# pomodoro-timer-shield.net
KiCad netlist of a schematic drawn in EAGLE
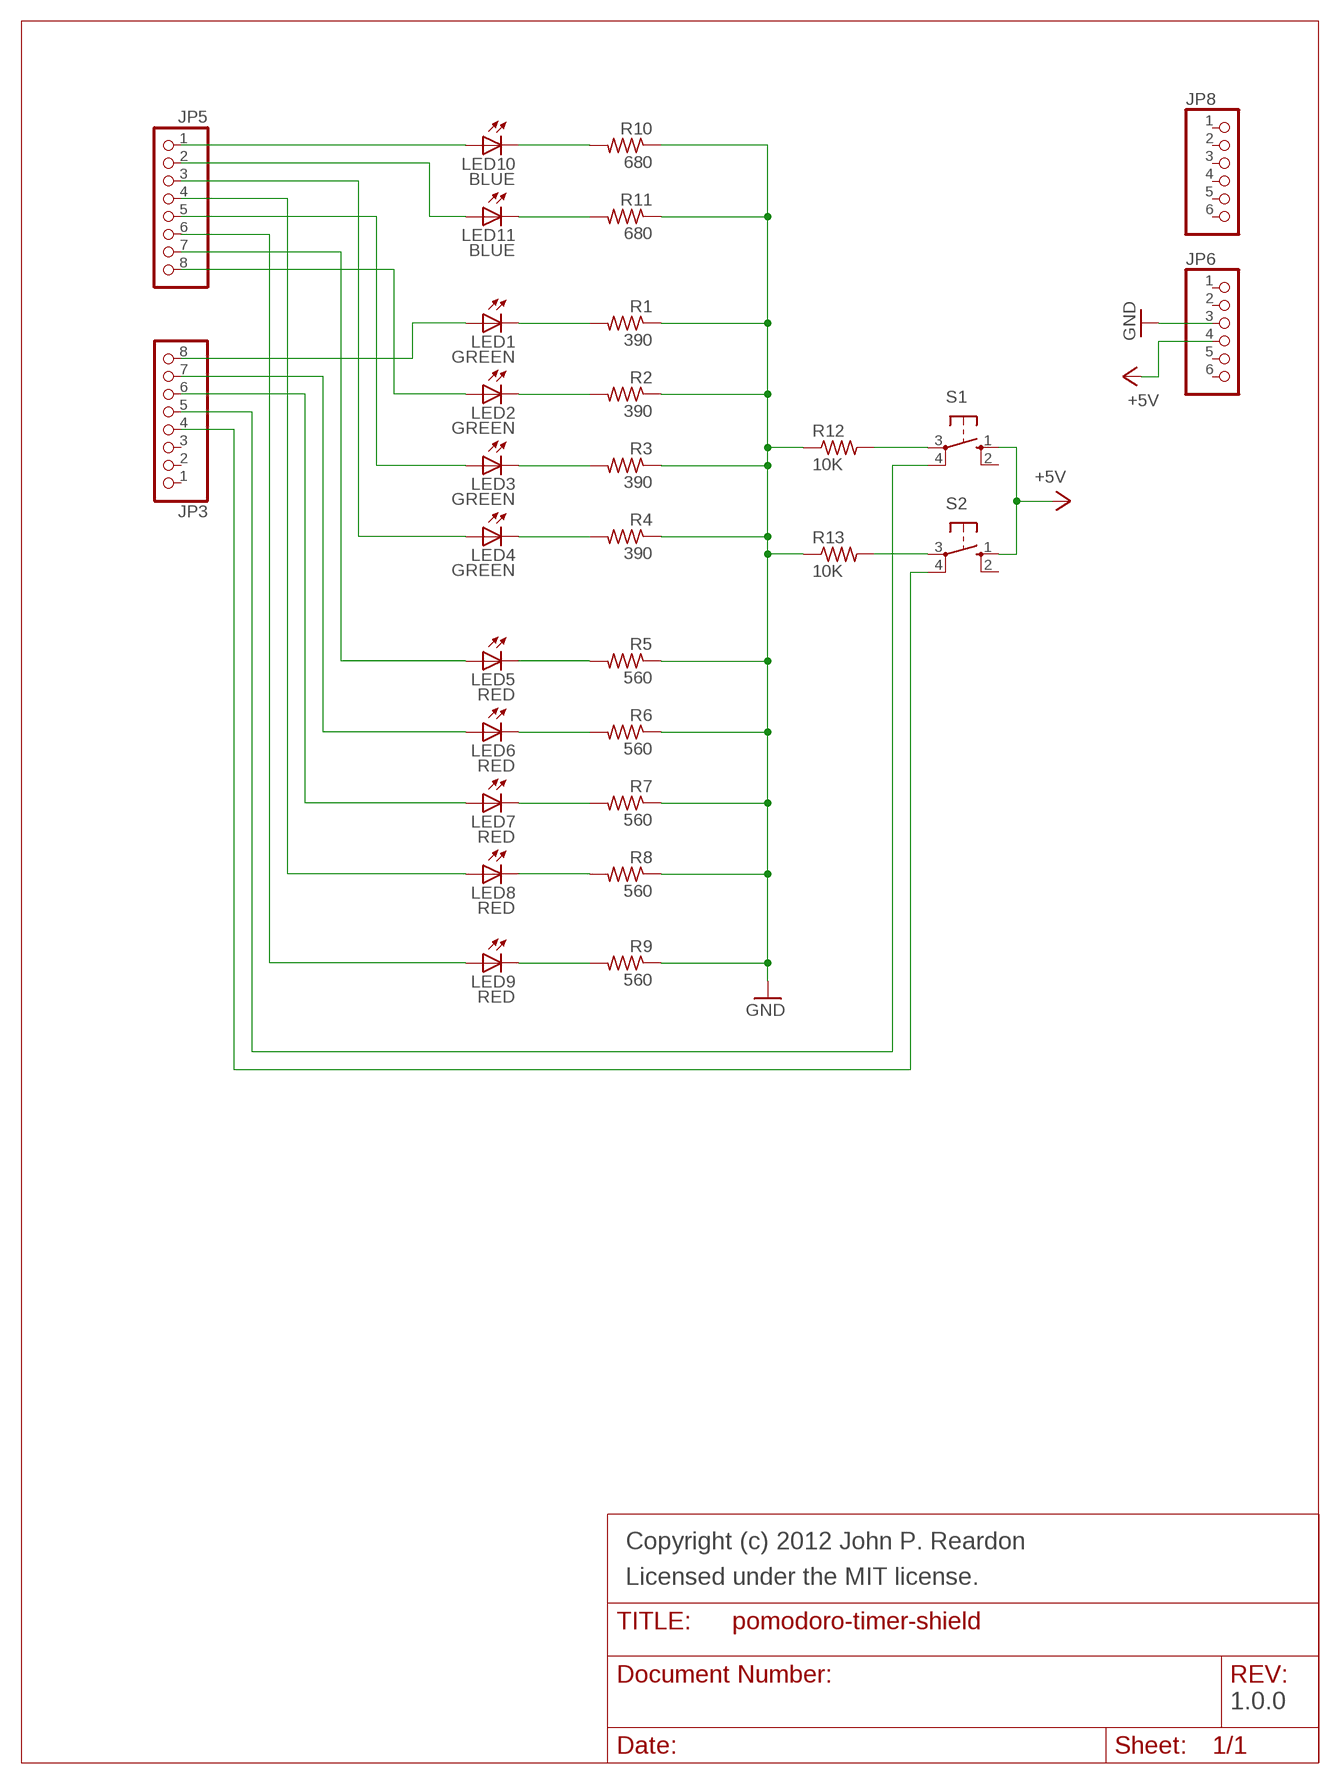
[diagram p0: schematic, sheet 1]

(export (version "E")
  (design (tool "Eeschema 10.0.6"))
  (components
    (comp (ref "JP3")
      (value "PINHD-1X8CLEANBIG")
      (footprint "eagle-import:1X08-CLEANBIG")
      (libsource (lib "eagle-import") (part "PINHD-1X8CLEANBIG"))
    )
    (comp (ref "JP5")
      (value "PINHD-1X8CLEANBIG")
      (footprint "eagle-import:1X08-CLEANBIG")
      (libsource (lib "eagle-import") (part "PINHD-1X8CLEANBIG"))
    )
    (comp (ref "JP6")
      (value "PINHD-1X6CB")
      (footprint "eagle-import:1X06-CLEANBIG")
      (libsource (lib "eagle-import") (part "PINHD-1X6CB"))
    )
    (comp (ref "JP8")
      (value "PINHD-1X6CB")
      (footprint "eagle-import:1X06-CLEANBIG")
      (libsource (lib "eagle-import") (part "PINHD-1X6CB"))
    )
    (comp (ref "LED1")
      (value "GREEN")
      (footprint "eagle-import:LED3MM")
      (libsource (lib "eagle-import") (part "LED3MM"))
    )
    (comp (ref "LED2")
      (value "GREEN")
      (footprint "eagle-import:LED3MM")
      (libsource (lib "eagle-import") (part "LED3MM"))
    )
    (comp (ref "LED3")
      (value "GREEN")
      (footprint "eagle-import:LED3MM")
      (libsource (lib "eagle-import") (part "LED3MM"))
    )
    (comp (ref "LED4")
      (value "GREEN")
      (footprint "eagle-import:LED3MM")
      (libsource (lib "eagle-import") (part "LED3MM"))
    )
    (comp (ref "LED5")
      (value "RED")
      (footprint "eagle-import:LED3MM")
      (libsource (lib "eagle-import") (part "LED3MM"))
    )
    (comp (ref "LED6")
      (value "RED")
      (footprint "eagle-import:LED3MM")
      (libsource (lib "eagle-import") (part "LED3MM"))
    )
    (comp (ref "LED7")
      (value "RED")
      (footprint "eagle-import:LED3MM")
      (libsource (lib "eagle-import") (part "LED3MM"))
    )
    (comp (ref "LED8")
      (value "RED")
      (footprint "eagle-import:LED3MM")
      (libsource (lib "eagle-import") (part "LED3MM"))
    )
    (comp (ref "LED9")
      (value "RED")
      (footprint "eagle-import:LED3MM")
      (libsource (lib "eagle-import") (part "LED3MM"))
    )
    (comp (ref "LED10")
      (value "BLUE")
      (footprint "eagle-import:LED3MM")
      (libsource (lib "eagle-import") (part "LED3MM"))
    )
    (comp (ref "LED11")
      (value "BLUE")
      (footprint "eagle-import:LED3MM")
      (libsource (lib "eagle-import") (part "LED3MM"))
    )
    (comp (ref "R1")
      (value "390")
      (footprint "eagle-import:0204_7")
      (libsource (lib "eagle-import") (part "R-US_0204/7"))
    )
    (comp (ref "R2")
      (value "390")
      (footprint "eagle-import:0204_7")
      (libsource (lib "eagle-import") (part "R-US_0204/7"))
    )
    (comp (ref "R3")
      (value "390")
      (footprint "eagle-import:0204_7")
      (libsource (lib "eagle-import") (part "R-US_0204/7"))
    )
    (comp (ref "R4")
      (value "390")
      (footprint "eagle-import:0204_7")
      (libsource (lib "eagle-import") (part "R-US_0204/7"))
    )
    (comp (ref "R5")
      (value "560")
      (footprint "eagle-import:0204_7")
      (libsource (lib "eagle-import") (part "R-US_0204/7"))
    )
    (comp (ref "R6")
      (value "560")
      (footprint "eagle-import:0204_7")
      (libsource (lib "eagle-import") (part "R-US_0204/7"))
    )
    (comp (ref "R7")
      (value "560")
      (footprint "eagle-import:0204_7")
      (libsource (lib "eagle-import") (part "R-US_0204/7"))
    )
    (comp (ref "R8")
      (value "560")
      (footprint "eagle-import:0204_7")
      (libsource (lib "eagle-import") (part "R-US_0204/7"))
    )
    (comp (ref "R9")
      (value "560")
      (footprint "eagle-import:0204_7")
      (libsource (lib "eagle-import") (part "R-US_0204/7"))
    )
    (comp (ref "R10")
      (value "680")
      (footprint "eagle-import:0204_7")
      (libsource (lib "eagle-import") (part "R-US_0204/7"))
    )
    (comp (ref "R11")
      (value "680")
      (footprint "eagle-import:0204_7")
      (libsource (lib "eagle-import") (part "R-US_0204/7"))
    )
    (comp (ref "R12")
      (value "10K")
      (footprint "eagle-import:0204_7")
      (libsource (lib "eagle-import") (part "R-US_0204/7"))
    )
    (comp (ref "R13")
      (value "10K")
      (footprint "eagle-import:0204_7")
      (libsource (lib "eagle-import") (part "R-US_0204/7"))
    )
    (comp (ref "S1")
      (value "10-XX")
      (footprint "eagle-import:B3F-10XX")
      (fields (field (name "MPN") "B3F-1000"))
      (libsource (lib "eagle-import") (part "10-XX"))
    )
    (comp (ref "S2")
      (value "10-XX")
      (footprint "eagle-import:B3F-10XX")
      (fields (field (name "MPN") "B3F-1000"))
      (libsource (lib "eagle-import") (part "10-XX"))
    )
  )
  (nets
    (net (code "1") (name "+5V") (class "Default")
      (node (ref "JP6") (pin "4") (pinfunction "4_4") (pintype "passive"))
      (node (ref "S1") (pin "1") (pinfunction "S_1") (pintype "passive"))
      (node (ref "S2") (pin "1") (pinfunction "S_1") (pintype "passive"))
    )
    (net (code "2") (name "GND") (class "Default")
      (node (ref "JP6") (pin "3") (pinfunction "3_3") (pintype "passive"))
      (node (ref "R1") (pin "1") (pinfunction "1_1") (pintype "passive"))
      (node (ref "R10") (pin "1") (pinfunction "1_1") (pintype "passive"))
      (node (ref "R11") (pin "1") (pinfunction "1_1") (pintype "passive"))
      (node (ref "R12") (pin "1") (pinfunction "1_1") (pintype "passive"))
      (node (ref "R13") (pin "1") (pinfunction "1_1") (pintype "passive"))
      (node (ref "R2") (pin "1") (pinfunction "1_1") (pintype "passive"))
      (node (ref "R3") (pin "1") (pinfunction "1_1") (pintype "passive"))
      (node (ref "R4") (pin "1") (pinfunction "1_1") (pintype "passive"))
      (node (ref "R5") (pin "1") (pinfunction "1_1") (pintype "passive"))
      (node (ref "R6") (pin "1") (pinfunction "1_1") (pintype "passive"))
      (node (ref "R7") (pin "1") (pinfunction "1_1") (pintype "passive"))
      (node (ref "R8") (pin "1") (pinfunction "1_1") (pintype "passive"))
      (node (ref "R9") (pin "1") (pinfunction "1_1") (pintype "passive"))
    )
    (net (code "3") (name "Net-(JP3-Pad6)") (class "Default")
      (node (ref "JP3") (pin "6") (pinfunction "6_6") (pintype "passive"))
      (node (ref "LED7") (pin "A") (pinfunction "A_A") (pintype "passive"))
    )
    (net (code "4") (name "Net-(JP3-Pad7)") (class "Default")
      (node (ref "JP3") (pin "7") (pinfunction "7_7") (pintype "passive"))
      (node (ref "LED6") (pin "A") (pinfunction "A_A") (pintype "passive"))
    )
    (net (code "5") (name "Net-(JP3-Pad8)") (class "Default")
      (node (ref "JP3") (pin "8") (pinfunction "8_8") (pintype "passive"))
      (node (ref "LED1") (pin "A") (pinfunction "A_A") (pintype "passive"))
    )
    (net (code "6") (name "Net-(JP5-Pad1)") (class "Default")
      (node (ref "JP5") (pin "1") (pinfunction "1_1") (pintype "passive"))
      (node (ref "LED10") (pin "A") (pinfunction "A_A") (pintype "passive"))
    )
    (net (code "7") (name "Net-(JP5-Pad2)") (class "Default")
      (node (ref "JP5") (pin "2") (pinfunction "2_2") (pintype "passive"))
      (node (ref "LED11") (pin "A") (pinfunction "A_A") (pintype "passive"))
    )
    (net (code "8") (name "Net-(JP5-Pad3)") (class "Default")
      (node (ref "JP5") (pin "3") (pinfunction "3_3") (pintype "passive"))
      (node (ref "LED4") (pin "A") (pinfunction "A_A") (pintype "passive"))
    )
    (net (code "9") (name "Net-(JP5-Pad4)") (class "Default")
      (node (ref "JP5") (pin "4") (pinfunction "4_4") (pintype "passive"))
      (node (ref "LED8") (pin "A") (pinfunction "A_A") (pintype "passive"))
    )
    (net (code "10") (name "Net-(JP5-Pad5)") (class "Default")
      (node (ref "JP5") (pin "5") (pinfunction "5_5") (pintype "passive"))
      (node (ref "LED3") (pin "A") (pinfunction "A_A") (pintype "passive"))
    )
    (net (code "11") (name "Net-(JP5-Pad6)") (class "Default")
      (node (ref "JP5") (pin "6") (pinfunction "6_6") (pintype "passive"))
      (node (ref "LED9") (pin "A") (pinfunction "A_A") (pintype "passive"))
    )
    (net (code "12") (name "Net-(JP5-Pad7)") (class "Default")
      (node (ref "JP5") (pin "7") (pinfunction "7_7") (pintype "passive"))
      (node (ref "LED5") (pin "A") (pinfunction "A_A") (pintype "passive"))
    )
    (net (code "13") (name "Net-(JP5-Pad8)") (class "Default")
      (node (ref "JP5") (pin "8") (pinfunction "8_8") (pintype "passive"))
      (node (ref "LED2") (pin "A") (pinfunction "A_A") (pintype "passive"))
    )
    (net (code "14") (name "Net-(LED1-C)") (class "Default")
      (node (ref "LED1") (pin "K") (pinfunction "C_K") (pintype "passive"))
      (node (ref "R1") (pin "2") (pinfunction "2_2") (pintype "passive"))
    )
    (net (code "15") (name "Net-(LED2-C)") (class "Default")
      (node (ref "LED2") (pin "K") (pinfunction "C_K") (pintype "passive"))
      (node (ref "R2") (pin "2") (pinfunction "2_2") (pintype "passive"))
    )
    (net (code "16") (name "Net-(LED3-C)") (class "Default")
      (node (ref "LED3") (pin "K") (pinfunction "C_K") (pintype "passive"))
      (node (ref "R3") (pin "2") (pinfunction "2_2") (pintype "passive"))
    )
    (net (code "17") (name "Net-(LED4-C)") (class "Default")
      (node (ref "LED4") (pin "K") (pinfunction "C_K") (pintype "passive"))
      (node (ref "R4") (pin "2") (pinfunction "2_2") (pintype "passive"))
    )
    (net (code "18") (name "Net-(LED5-C)") (class "Default")
      (node (ref "LED5") (pin "K") (pinfunction "C_K") (pintype "passive"))
      (node (ref "R5") (pin "2") (pinfunction "2_2") (pintype "passive"))
    )
    (net (code "19") (name "Net-(LED6-C)") (class "Default")
      (node (ref "LED6") (pin "K") (pinfunction "C_K") (pintype "passive"))
      (node (ref "R6") (pin "2") (pinfunction "2_2") (pintype "passive"))
    )
    (net (code "20") (name "Net-(LED7-C)") (class "Default")
      (node (ref "LED7") (pin "K") (pinfunction "C_K") (pintype "passive"))
      (node (ref "R7") (pin "2") (pinfunction "2_2") (pintype "passive"))
    )
    (net (code "21") (name "Net-(LED8-C)") (class "Default")
      (node (ref "LED8") (pin "K") (pinfunction "C_K") (pintype "passive"))
      (node (ref "R8") (pin "2") (pinfunction "2_2") (pintype "passive"))
    )
    (net (code "22") (name "Net-(LED9-C)") (class "Default")
      (node (ref "LED9") (pin "K") (pinfunction "C_K") (pintype "passive"))
      (node (ref "R9") (pin "2") (pinfunction "2_2") (pintype "passive"))
    )
    (net (code "23") (name "Net-(LED10-C)") (class "Default")
      (node (ref "LED10") (pin "K") (pinfunction "C_K") (pintype "passive"))
      (node (ref "R10") (pin "2") (pinfunction "2_2") (pintype "passive"))
    )
    (net (code "24") (name "Net-(LED11-C)") (class "Default")
      (node (ref "LED11") (pin "K") (pinfunction "C_K") (pintype "passive"))
      (node (ref "R11") (pin "2") (pinfunction "2_2") (pintype "passive"))
    )
    (net (code "25") (name "Net-(S1-P)") (class "Default")
      (node (ref "R12") (pin "2") (pinfunction "2_2") (pintype "passive"))
      (node (ref "S1") (pin "3") (pinfunction "P_3") (pintype "passive"))
    )
    (net (code "26") (name "Net-(S1-P1)") (class "Default")
      (node (ref "JP3") (pin "5") (pinfunction "5_5") (pintype "passive"))
      (node (ref "S1") (pin "4") (pinfunction "P1_4") (pintype "passive"))
    )
    (net (code "27") (name "Net-(S2-P)") (class "Default")
      (node (ref "R13") (pin "2") (pinfunction "2_2") (pintype "passive"))
      (node (ref "S2") (pin "3") (pinfunction "P_3") (pintype "passive"))
    )
    (net (code "28") (name "Net-(S2-P1)") (class "Default")
      (node (ref "JP3") (pin "4") (pinfunction "4_4") (pintype "passive"))
      (node (ref "S2") (pin "4") (pinfunction "P1_4") (pintype "passive"))
    )
    (net (code "29") (name "unconnected-(JP3-Pad1)") (class "Default")
      (node (ref "JP3") (pin "1") (pinfunction "1_1") (pintype "passive"))
    )
    (net (code "30") (name "unconnected-(JP3-Pad2)") (class "Default")
      (node (ref "JP3") (pin "2") (pinfunction "2_2") (pintype "passive"))
    )
    (net (code "31") (name "unconnected-(JP3-Pad3)") (class "Default")
      (node (ref "JP3") (pin "3") (pinfunction "3_3") (pintype "passive"))
    )
    (net (code "32") (name "unconnected-(JP6-Pad1)") (class "Default")
      (node (ref "JP6") (pin "1") (pinfunction "1_1") (pintype "passive"))
    )
    (net (code "33") (name "unconnected-(JP6-Pad2)") (class "Default")
      (node (ref "JP6") (pin "2") (pinfunction "2_2") (pintype "passive"))
    )
    (net (code "34") (name "unconnected-(JP6-Pad5)") (class "Default")
      (node (ref "JP6") (pin "5") (pinfunction "5_5") (pintype "passive"))
    )
    (net (code "35") (name "unconnected-(JP6-Pad6)") (class "Default")
      (node (ref "JP6") (pin "6") (pinfunction "6_6") (pintype "passive"))
    )
    (net (code "36") (name "unconnected-(JP8-Pad1)") (class "Default")
      (node (ref "JP8") (pin "1") (pinfunction "1_1") (pintype "passive"))
    )
    (net (code "37") (name "unconnected-(JP8-Pad2)") (class "Default")
      (node (ref "JP8") (pin "2") (pinfunction "2_2") (pintype "passive"))
    )
    (net (code "38") (name "unconnected-(JP8-Pad3)") (class "Default")
      (node (ref "JP8") (pin "3") (pinfunction "3_3") (pintype "passive"))
    )
    (net (code "39") (name "unconnected-(JP8-Pad4)") (class "Default")
      (node (ref "JP8") (pin "4") (pinfunction "4_4") (pintype "passive"))
    )
    (net (code "40") (name "unconnected-(JP8-Pad5)") (class "Default")
      (node (ref "JP8") (pin "5") (pinfunction "5_5") (pintype "passive"))
    )
    (net (code "41") (name "unconnected-(JP8-Pad6)") (class "Default")
      (node (ref "JP8") (pin "6") (pinfunction "6_6") (pintype "passive"))
    )
    (net (code "42") (name "unconnected-(S1-S1-Pad2)") (class "Default")
      (node (ref "S1") (pin "2") (pinfunction "S1_2") (pintype "passive"))
    )
    (net (code "43") (name "unconnected-(S2-S1-Pad2)") (class "Default")
      (node (ref "S2") (pin "2") (pinfunction "S1_2") (pintype "passive"))
    )
  )
)
